# OpenRuchePCB.net
KiCad netlist of a schematic drawn in EasyEDA
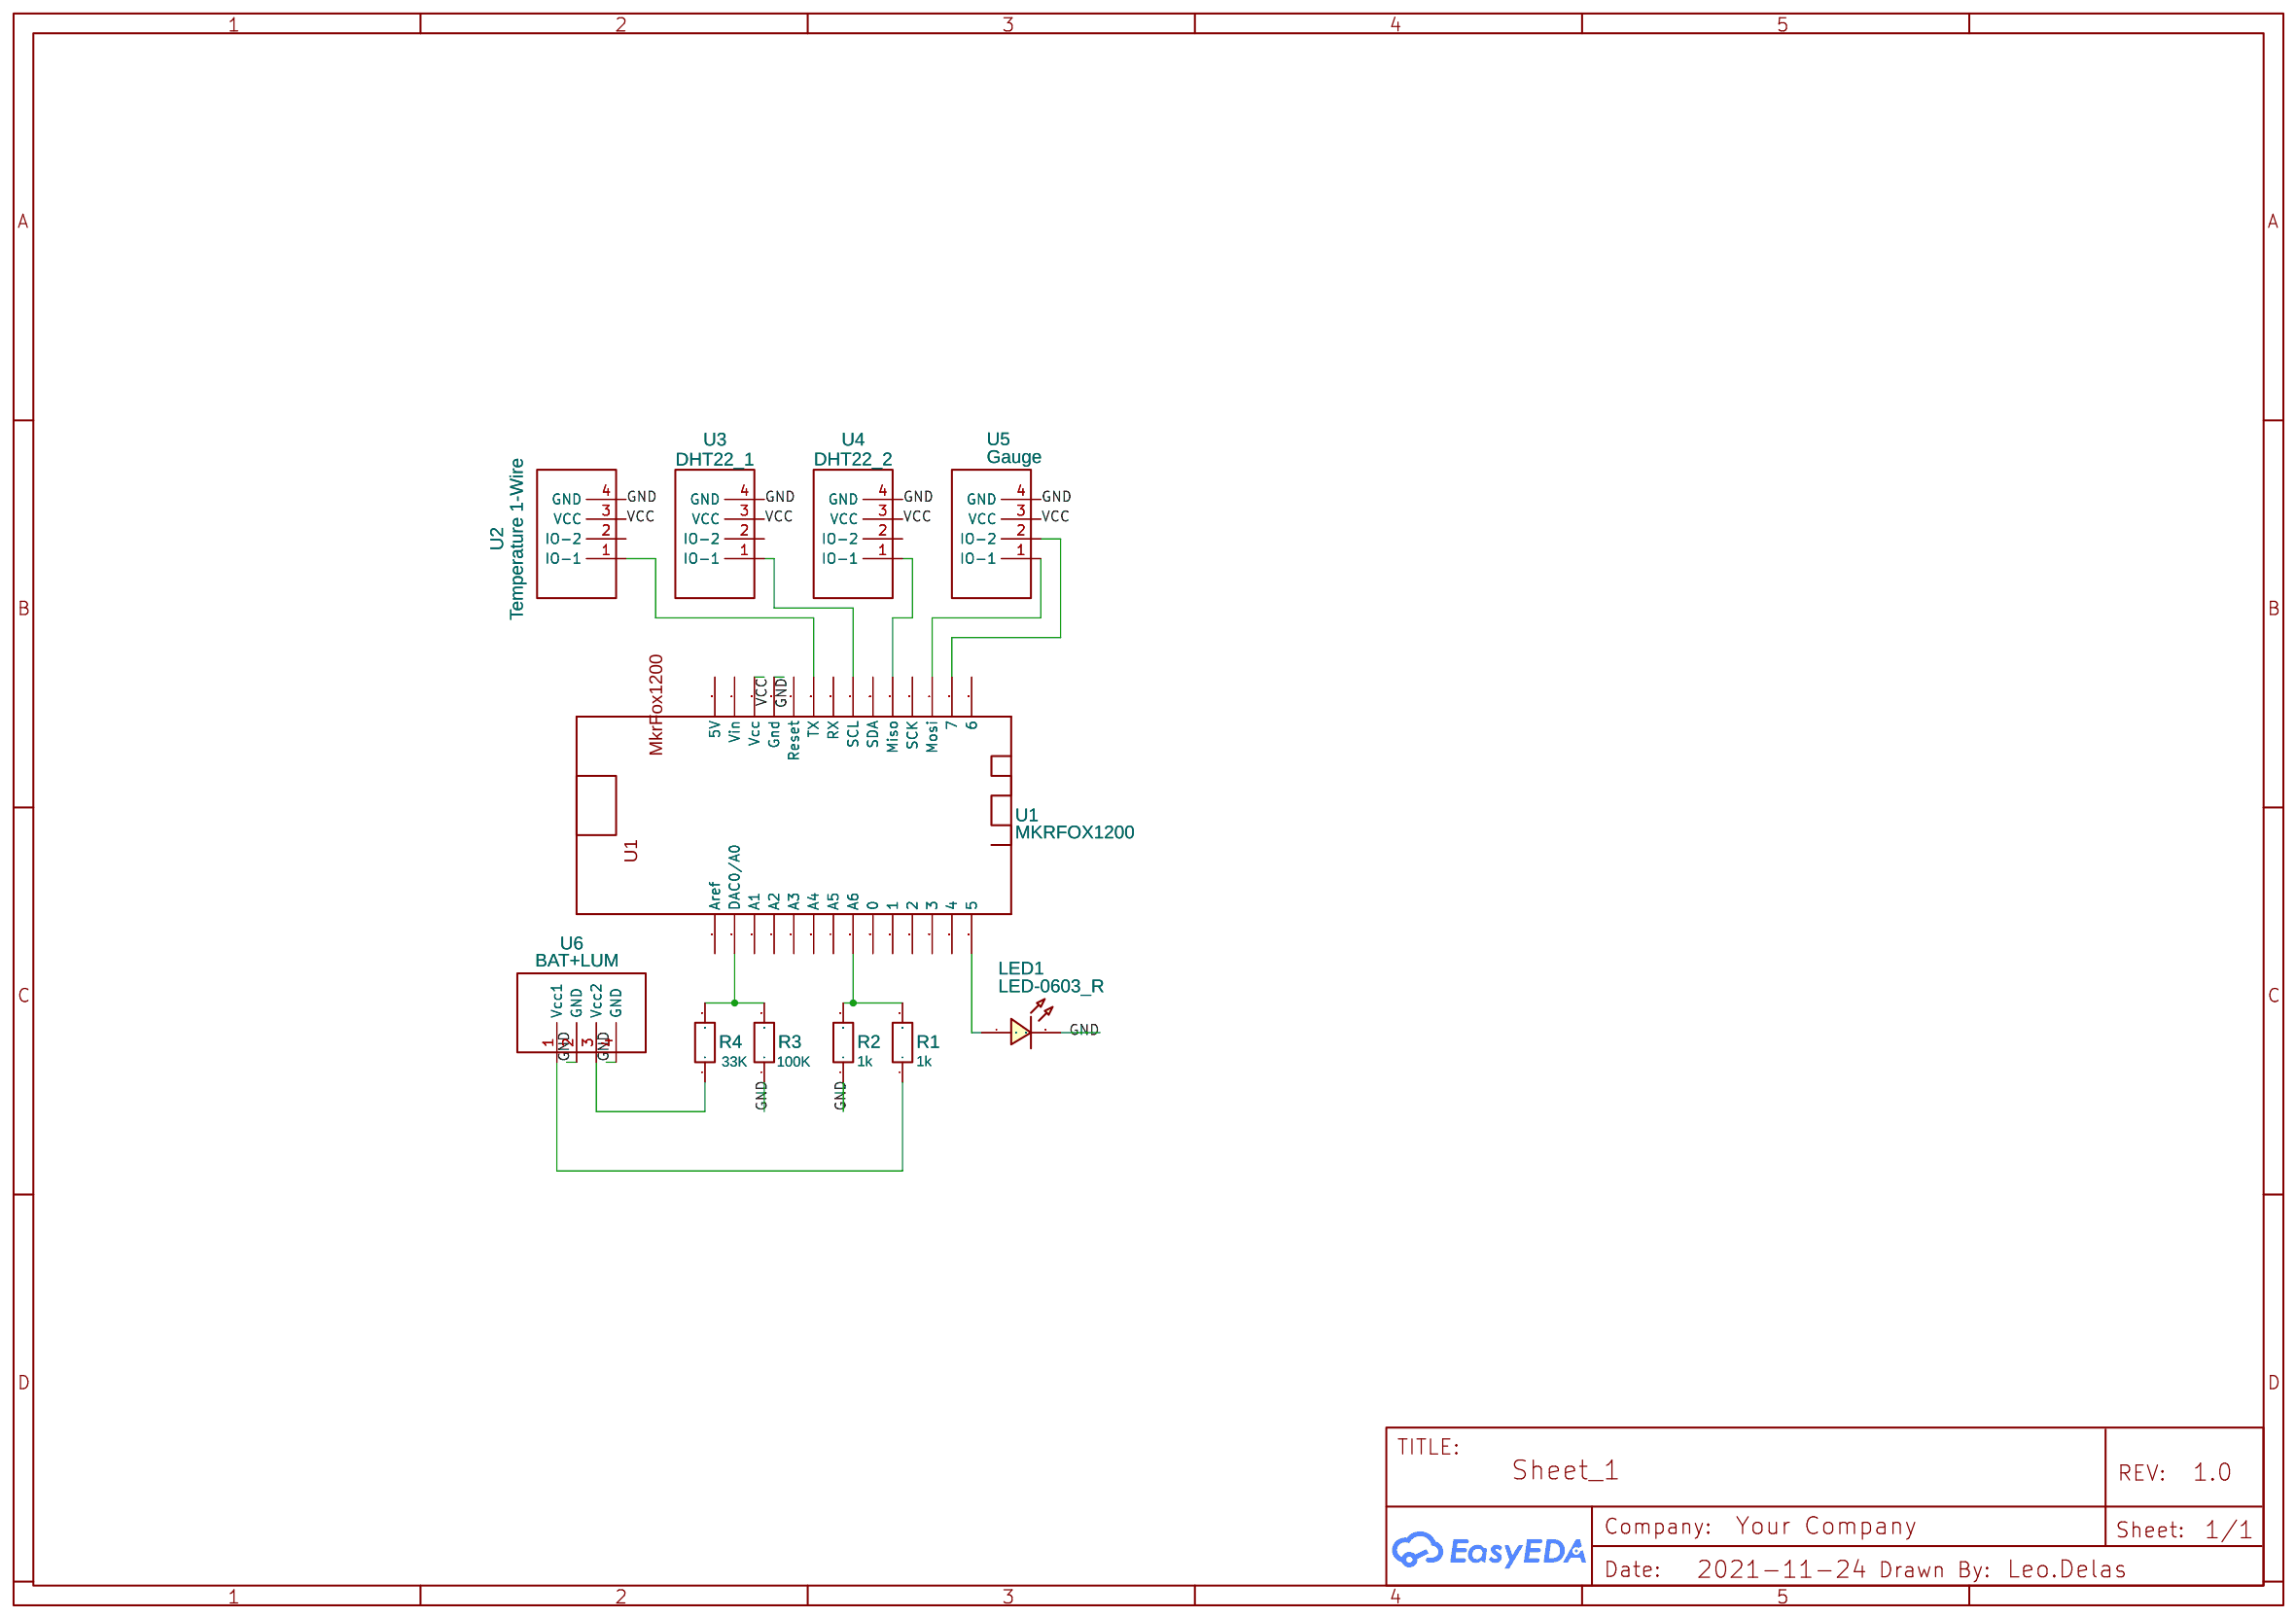
[diagram p0: schematic sheet]

(export (version "E")
  (design (tool "Eeschema 10.0.6"))
  (components
    (comp (ref "LED1")
      (value "LED-0603_R")
      (fields
        (field (name "BOM_Manufacturer Part") "19-217/R6C-AL1M2VY/3T")
        (field (name "BOM_Supplier Part") "C72044")
      )
      (libsource (lib "") (part "LED-0603_R"))
    )
    (comp (ref "R1") (value "1k") (libsource (lib "") (part "R_0603_EU")))
    (comp (ref "R2") (value "1k") (libsource (lib "") (part "R_0603_EU")))
    (comp (ref "R3") (value "100K") (libsource (lib "") (part "R_0603_EU")))
    (comp (ref "R4") (value "33K") (libsource (lib "") (part "R_0603_EU")))
    (comp (ref "U1") (value "MKRFOX1200") (libsource (lib "") (part "MKRFOX1200")))
    (comp (ref "U2")
      (value "Temperature 1-Wire")
      (fields (field (name "BOM_Supplier Part") "undefined"))
      (libsource (lib "") (part "Grove - GPIO"))
    )
    (comp (ref "U3")
      (value "DHT22_1")
      (fields (field (name "BOM_Supplier Part") "undefined"))
      (libsource (lib "") (part "Grove - GPIO"))
    )
    (comp (ref "U4")
      (value "DHT22_2")
      (fields (field (name "BOM_Supplier Part") "undefined"))
      (libsource (lib "") (part "Grove - GPIO"))
    )
    (comp (ref "U5")
      (value "Gauge")
      (fields (field (name "BOM_Supplier Part") "undefined"))
      (libsource (lib "") (part "Grove - GPIO"))
    )
    (comp (ref "U6")
      (value "BAT+LUM")
      (fields (field (name "BOM_Supplier Part") "undefined"))
      (libsource (lib "") (part "Grove - GPIO_1"))
    )
  )
  (nets
    (net (code "1") (name "/GND") (class "Default")
      (node (ref "LED1") (pin "2") (pinfunction "2_2") (pintype "unspecified"))
      (node (ref "R2") (pin "1") (pinfunction "1_1") (pintype "unspecified"))
      (node (ref "R3") (pin "1") (pinfunction "1_1") (pintype "unspecified"))
      (node (ref "U1") (pin "25") (pinfunction "Gnd_25") (pintype "bidirectional"))
      (node (ref "U2") (pin "4") (pinfunction "GND_4") (pintype "unspecified"))
      (node (ref "U3") (pin "4") (pinfunction "GND_4") (pintype "unspecified"))
      (node (ref "U4") (pin "4") (pinfunction "GND_4") (pintype "unspecified"))
      (node (ref "U5") (pin "4") (pinfunction "GND_4") (pintype "unspecified"))
      (node (ref "U6") (pin "2") (pinfunction "GND_2") (pintype "unspecified"))
      (node (ref "U6") (pin "4") (pinfunction "GND_4") (pintype "unspecified"))
    )
    (net (code "2") (name "/VCC") (class "Default")
      (node (ref "U1") (pin "26") (pinfunction "Vcc_26") (pintype "bidirectional"))
      (node (ref "U2") (pin "3") (pinfunction "VCC_3") (pintype "unspecified"))
      (node (ref "U3") (pin "3") (pinfunction "VCC_3") (pintype "unspecified"))
      (node (ref "U4") (pin "3") (pinfunction "VCC_3") (pintype "unspecified"))
      (node (ref "U5") (pin "3") (pinfunction "VCC_3") (pintype "unspecified"))
    )
    (net (code "3") (name "Net-(U1-5)") (class "Default")
      (node (ref "LED1") (pin "1") (pinfunction "1_1") (pintype "unspecified"))
      (node (ref "U1") (pin "14") (pinfunction "5_14") (pintype "bidirectional"))
    )
    (net (code "4") (name "Net-(U1-7)") (class "Default")
      (node (ref "U1") (pin "16") (pinfunction "7_16") (pintype "bidirectional"))
      (node (ref "U5") (pin "2") (pinfunction "IO-2_2") (pintype "unspecified"))
    )
    (net (code "5") (name "Net-(U1-A6)") (class "Default")
      (node (ref "R1") (pin "2") (pinfunction "2_2") (pintype "unspecified"))
      (node (ref "R2") (pin "2") (pinfunction "2_2") (pintype "unspecified"))
      (node (ref "U1") (pin "8") (pinfunction "A6_8") (pintype "bidirectional"))
    )
    (net (code "6") (name "Net-(U1-DAC0{slash}A0)") (class "Default")
      (node (ref "R3") (pin "2") (pinfunction "2_2") (pintype "unspecified"))
      (node (ref "R4") (pin "2") (pinfunction "2_2") (pintype "unspecified"))
      (node (ref "U1") (pin "2") (pinfunction "DAC0/A0_2") (pintype "bidirectional"))
    )
    (net (code "7") (name "Net-(U1-Miso)") (class "Default")
      (node (ref "U1") (pin "19") (pinfunction "Miso_19") (pintype "bidirectional"))
      (node (ref "U4") (pin "1") (pinfunction "IO-1_1") (pintype "unspecified"))
    )
    (net (code "8") (name "Net-(U1-Mosi)") (class "Default")
      (node (ref "U1") (pin "17") (pinfunction "Mosi_17") (pintype "bidirectional"))
      (node (ref "U5") (pin "1") (pinfunction "IO-1_1") (pintype "unspecified"))
    )
    (net (code "9") (name "Net-(U1-SCL)") (class "Default")
      (node (ref "U1") (pin "21") (pinfunction "SCL_21") (pintype "bidirectional"))
      (node (ref "U3") (pin "1") (pinfunction "IO-1_1") (pintype "unspecified"))
    )
    (net (code "10") (name "Net-(U1-TX)") (class "Default")
      (node (ref "U1") (pin "23") (pinfunction "TX_23") (pintype "bidirectional"))
      (node (ref "U2") (pin "1") (pinfunction "IO-1_1") (pintype "unspecified"))
    )
    (net (code "11") (name "Net-(U6-Vcc1)") (class "Default")
      (node (ref "R1") (pin "1") (pinfunction "1_1") (pintype "unspecified"))
      (node (ref "U6") (pin "1") (pinfunction "Vcc1_1") (pintype "unspecified"))
    )
    (net (code "12") (name "Net-(U6-Vcc2)") (class "Default")
      (node (ref "R4") (pin "1") (pinfunction "1_1") (pintype "unspecified"))
      (node (ref "U6") (pin "3") (pinfunction "Vcc2_3") (pintype "unspecified"))
    )
    (net (code "13") (name "unconnected-(U1-0-Pad9)") (class "Default")
      (node (ref "U1") (pin "9") (pinfunction "0_9") (pintype "bidirectional"))
    )
    (net (code "14") (name "unconnected-(U1-1-Pad10)") (class "Default")
      (node (ref "U1") (pin "10") (pinfunction "1_10") (pintype "bidirectional"))
    )
    (net (code "15") (name "unconnected-(U1-2-Pad11)") (class "Default")
      (node (ref "U1") (pin "11") (pinfunction "2_11") (pintype "bidirectional"))
    )
    (net (code "16") (name "unconnected-(U1-3-Pad12)") (class "Default")
      (node (ref "U1") (pin "12") (pinfunction "3_12") (pintype "bidirectional"))
    )
    (net (code "17") (name "unconnected-(U1-4-Pad13)") (class "Default")
      (node (ref "U1") (pin "13") (pinfunction "4_13") (pintype "bidirectional"))
    )
    (net (code "18") (name "unconnected-(U1-5V-Pad28)") (class "Default")
      (node (ref "U1") (pin "28") (pinfunction "5V_28") (pintype "bidirectional"))
    )
    (net (code "19") (name "unconnected-(U1-6-Pad15)") (class "Default")
      (node (ref "U1") (pin "15") (pinfunction "6_15") (pintype "bidirectional"))
    )
    (net (code "20") (name "unconnected-(U1-A1-Pad3)") (class "Default")
      (node (ref "U1") (pin "3") (pinfunction "A1_3") (pintype "bidirectional"))
    )
    (net (code "21") (name "unconnected-(U1-A2-Pad4)") (class "Default")
      (node (ref "U1") (pin "4") (pinfunction "A2_4") (pintype "bidirectional"))
    )
    (net (code "22") (name "unconnected-(U1-A3-Pad5)") (class "Default")
      (node (ref "U1") (pin "5") (pinfunction "A3_5") (pintype "bidirectional"))
    )
    (net (code "23") (name "unconnected-(U1-A4-Pad6)") (class "Default")
      (node (ref "U1") (pin "6") (pinfunction "A4_6") (pintype "bidirectional"))
    )
    (net (code "24") (name "unconnected-(U1-A5-Pad7)") (class "Default")
      (node (ref "U1") (pin "7") (pinfunction "A5_7") (pintype "bidirectional"))
    )
    (net (code "25") (name "unconnected-(U1-Aref-Pad1)") (class "Default")
      (node (ref "U1") (pin "1") (pinfunction "Aref_1") (pintype "bidirectional"))
    )
    (net (code "26") (name "unconnected-(U1-RX-Pad22)") (class "Default")
      (node (ref "U1") (pin "22") (pinfunction "RX_22") (pintype "bidirectional"))
    )
    (net (code "27") (name "unconnected-(U1-Reset-Pad24)") (class "Default")
      (node (ref "U1") (pin "24") (pinfunction "Reset_24") (pintype "bidirectional"))
    )
    (net (code "28") (name "unconnected-(U1-SCK-Pad18)") (class "Default")
      (node (ref "U1") (pin "18") (pinfunction "SCK_18") (pintype "bidirectional"))
    )
    (net (code "29") (name "unconnected-(U1-SDA-Pad20)") (class "Default")
      (node (ref "U1") (pin "20") (pinfunction "SDA_20") (pintype "bidirectional"))
    )
    (net (code "30") (name "unconnected-(U1-Vin-Pad27)") (class "Default")
      (node (ref "U1") (pin "27") (pinfunction "Vin_27") (pintype "bidirectional"))
    )
    (net (code "31") (name "unconnected-(U2-IO-2-Pad2)") (class "Default")
      (node (ref "U2") (pin "2") (pinfunction "IO-2_2") (pintype "unspecified"))
    )
    (net (code "32") (name "unconnected-(U3-IO-2-Pad2)") (class "Default")
      (node (ref "U3") (pin "2") (pinfunction "IO-2_2") (pintype "unspecified"))
    )
    (net (code "33") (name "unconnected-(U4-IO-2-Pad2)") (class "Default")
      (node (ref "U4") (pin "2") (pinfunction "IO-2_2") (pintype "unspecified"))
    )
  )
)
